# MCU.net
KiCad netlist of a schematic drawn in Altium Designer
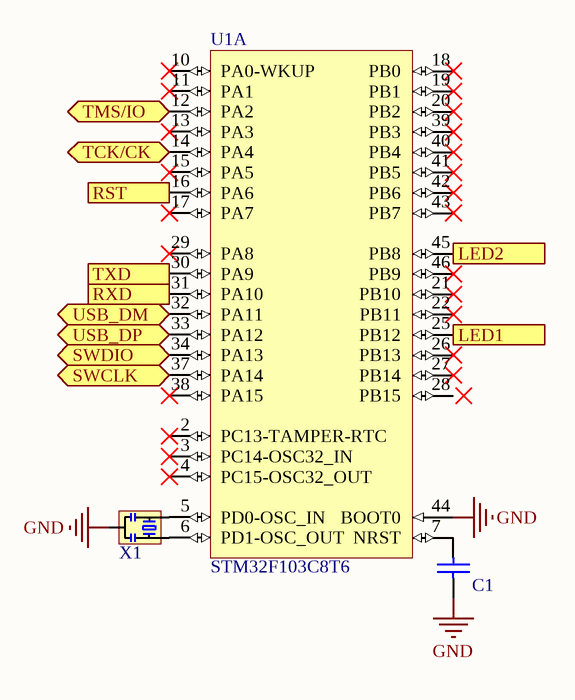
[diagram p0: MCU.SchDoc]

(export (version "E")
  (design (tool "Eeschema 10.0.6"))
  (components
    (comp (ref "C1")
      (value "100nF")
      (footprint "CAP-0603")
      (description "贴片电容")
      (libsource (lib "Power_Lib_Altium") (part "CAP"))
    )
    (comp (ref "U1")
      (value "STM32F103C8T6")
      (footprint "LQFP_48")
      (description "单片机")
      (fields (field (name "PARTNUMBER") "STM32F100C8T6B"))
      (libsource (lib "Power_Lib_Altium") (part "STM32F103Cx"))
    )
    (comp (ref "X1")
      (value "8MHz")
      (footprint "CSTCE_G(A)村田晶振")
      (description "有源晶振")
      (libsource (lib "Power_Lib_Altium") (part "XTAL"))
    )
  )
  (nets
    (net (code "1") (name "/LED1") (class "Default")
      (node (ref "U1") (pin "25") (pinfunction "PB12_25") (pintype "bidirectional"))
    )
    (net (code "2") (name "/LED2") (class "Default")
      (node (ref "U1") (pin "45") (pinfunction "PB8_45") (pintype "bidirectional"))
    )
    (net (code "3") (name "/RST") (class "Default")
      (node (ref "U1") (pin "16") (pinfunction "PA6_16") (pintype "bidirectional"))
    )
    (net (code "4") (name "/RXD") (class "Default")
      (node (ref "U1") (pin "31") (pinfunction "PA10_31") (pintype "bidirectional"))
    )
    (net (code "5") (name "/SWCLK") (class "Default")
      (node (ref "U1") (pin "37") (pinfunction "PA14_37") (pintype "bidirectional"))
    )
    (net (code "6") (name "/SWDIO") (class "Default")
      (node (ref "U1") (pin "34") (pinfunction "PA13_34") (pintype "bidirectional"))
    )
    (net (code "7") (name "/TCK{slash}CK") (class "Default")
      (node (ref "U1") (pin "14") (pinfunction "PA4_14") (pintype "bidirectional"))
    )
    (net (code "8") (name "/TMS{slash}IO") (class "Default")
      (node (ref "U1") (pin "12") (pinfunction "PA2_12") (pintype "bidirectional"))
    )
    (net (code "9") (name "/TXD") (class "Default")
      (node (ref "U1") (pin "30") (pinfunction "PA9_30") (pintype "bidirectional"))
    )
    (net (code "10") (name "/USB_DM") (class "Default")
      (node (ref "U1") (pin "32") (pinfunction "PA11_32") (pintype "bidirectional"))
    )
    (net (code "11") (name "/USB_DP") (class "Default")
      (node (ref "U1") (pin "33") (pinfunction "PA12_33") (pintype "bidirectional"))
    )
    (net (code "12") (name "GND") (class "Default")
      (node (ref "C1") (pin "2") (pinfunction "2_2") (pintype "passive"))
      (node (ref "U1") (pin "44") (pinfunction "BOOT0_44") (pintype "input"))
      (node (ref "X1") (pin "2") (pinfunction "GND_2") (pintype "passive"))
    )
    (net (code "13") (name "Net-(U1A-NRST)") (class "Default")
      (node (ref "C1") (pin "1") (pinfunction "1_1") (pintype "passive"))
      (node (ref "U1") (pin "7") (pinfunction "NRST_7") (pintype "bidirectional"))
    )
    (net (code "14") (name "Net-(U1A-PD0-OSC_IN)") (class "Default")
      (node (ref "U1") (pin "5") (pinfunction "PD0-OSC_IN_5") (pintype "bidirectional"))
      (node (ref "X1") (pin "1") (pinfunction "OSC1_1") (pintype "passive"))
    )
    (net (code "15") (name "Net-(U1A-PD1-OSC_OUT)") (class "Default")
      (node (ref "U1") (pin "6") (pinfunction "PD1-OSC_OUT_6") (pintype "bidirectional"))
      (node (ref "X1") (pin "3") (pinfunction "OSC2_3") (pintype "passive"))
    )
    (net (code "16") (name "unconnected-(U1A-PA0-WKUP-Pad10)") (class "Default")
      (node (ref "U1") (pin "10") (pinfunction "PA0-WKUP_10") (pintype "bidirectional+no_connect"))
    )
    (net (code "17") (name "unconnected-(U1A-PA1-Pad11)") (class "Default")
      (node (ref "U1") (pin "11") (pinfunction "PA1_11") (pintype "bidirectional+no_connect"))
    )
    (net (code "18") (name "unconnected-(U1A-PA3-Pad13)") (class "Default")
      (node (ref "U1") (pin "13") (pinfunction "PA3_13") (pintype "bidirectional+no_connect"))
    )
    (net (code "19") (name "unconnected-(U1A-PA5-Pad15)") (class "Default")
      (node (ref "U1") (pin "15") (pinfunction "PA5_15") (pintype "bidirectional+no_connect"))
    )
    (net (code "20") (name "unconnected-(U1A-PA7-Pad17)") (class "Default")
      (node (ref "U1") (pin "17") (pinfunction "PA7_17") (pintype "bidirectional+no_connect"))
    )
    (net (code "21") (name "unconnected-(U1A-PA8-Pad29)") (class "Default")
      (node (ref "U1") (pin "29") (pinfunction "PA8_29") (pintype "bidirectional+no_connect"))
    )
    (net (code "22") (name "unconnected-(U1A-PA15-Pad38)") (class "Default")
      (node (ref "U1") (pin "38") (pinfunction "PA15_38") (pintype "bidirectional+no_connect"))
    )
    (net (code "23") (name "unconnected-(U1A-PB0-Pad18)") (class "Default")
      (node (ref "U1") (pin "18") (pinfunction "PB0_18") (pintype "bidirectional+no_connect"))
    )
    (net (code "24") (name "unconnected-(U1A-PB1-Pad19)") (class "Default")
      (node (ref "U1") (pin "19") (pinfunction "PB1_19") (pintype "bidirectional+no_connect"))
    )
    (net (code "25") (name "unconnected-(U1A-PB2-Pad20)") (class "Default")
      (node (ref "U1") (pin "20") (pinfunction "PB2_20") (pintype "bidirectional+no_connect"))
    )
    (net (code "26") (name "unconnected-(U1A-PB3-Pad39)") (class "Default")
      (node (ref "U1") (pin "39") (pinfunction "PB3_39") (pintype "bidirectional+no_connect"))
    )
    (net (code "27") (name "unconnected-(U1A-PB4-Pad40)") (class "Default")
      (node (ref "U1") (pin "40") (pinfunction "PB4_40") (pintype "bidirectional+no_connect"))
    )
    (net (code "28") (name "unconnected-(U1A-PB5-Pad41)") (class "Default")
      (node (ref "U1") (pin "41") (pinfunction "PB5_41") (pintype "bidirectional+no_connect"))
    )
    (net (code "29") (name "unconnected-(U1A-PB6-Pad42)") (class "Default")
      (node (ref "U1") (pin "42") (pinfunction "PB6_42") (pintype "bidirectional+no_connect"))
    )
    (net (code "30") (name "unconnected-(U1A-PB7-Pad43)") (class "Default")
      (node (ref "U1") (pin "43") (pinfunction "PB7_43") (pintype "bidirectional+no_connect"))
    )
    (net (code "31") (name "unconnected-(U1A-PB9-Pad46)") (class "Default")
      (node (ref "U1") (pin "46") (pinfunction "PB9_46") (pintype "bidirectional+no_connect"))
    )
    (net (code "32") (name "unconnected-(U1A-PB10-Pad21)") (class "Default")
      (node (ref "U1") (pin "21") (pinfunction "PB10_21") (pintype "bidirectional+no_connect"))
    )
    (net (code "33") (name "unconnected-(U1A-PB11-Pad22)") (class "Default")
      (node (ref "U1") (pin "22") (pinfunction "PB11_22") (pintype "bidirectional+no_connect"))
    )
    (net (code "34") (name "unconnected-(U1A-PB13-Pad26)") (class "Default")
      (node (ref "U1") (pin "26") (pinfunction "PB13_26") (pintype "bidirectional+no_connect"))
    )
    (net (code "35") (name "unconnected-(U1A-PB14-Pad27)") (class "Default")
      (node (ref "U1") (pin "27") (pinfunction "PB14_27") (pintype "bidirectional+no_connect"))
    )
    (net (code "36") (name "unconnected-(U1A-PB15-Pad28)") (class "Default")
      (node (ref "U1") (pin "28") (pinfunction "PB15_28") (pintype "bidirectional"))
    )
    (net (code "37") (name "unconnected-(U1A-PC13-TAMPER-RTC-Pad2)") (class "Default")
      (node (ref "U1") (pin "2") (pinfunction "PC13-TAMPER-RTC_2") (pintype "bidirectional+no_connect"))
    )
    (net (code "38") (name "unconnected-(U1A-PC14-OSC32_IN-Pad3)") (class "Default")
      (node (ref "U1") (pin "3") (pinfunction "PC14-OSC32_IN_3") (pintype "bidirectional+no_connect"))
    )
    (net (code "39") (name "unconnected-(U1A-PC15-OSC32_OUT-Pad4)") (class "Default")
      (node (ref "U1") (pin "4") (pinfunction "PC15-OSC32_OUT_4") (pintype "bidirectional+no_connect"))
    )
  )
)
